# AEMLIC-V1.net
KiCad netlist of a schematic drawn in EAGLE
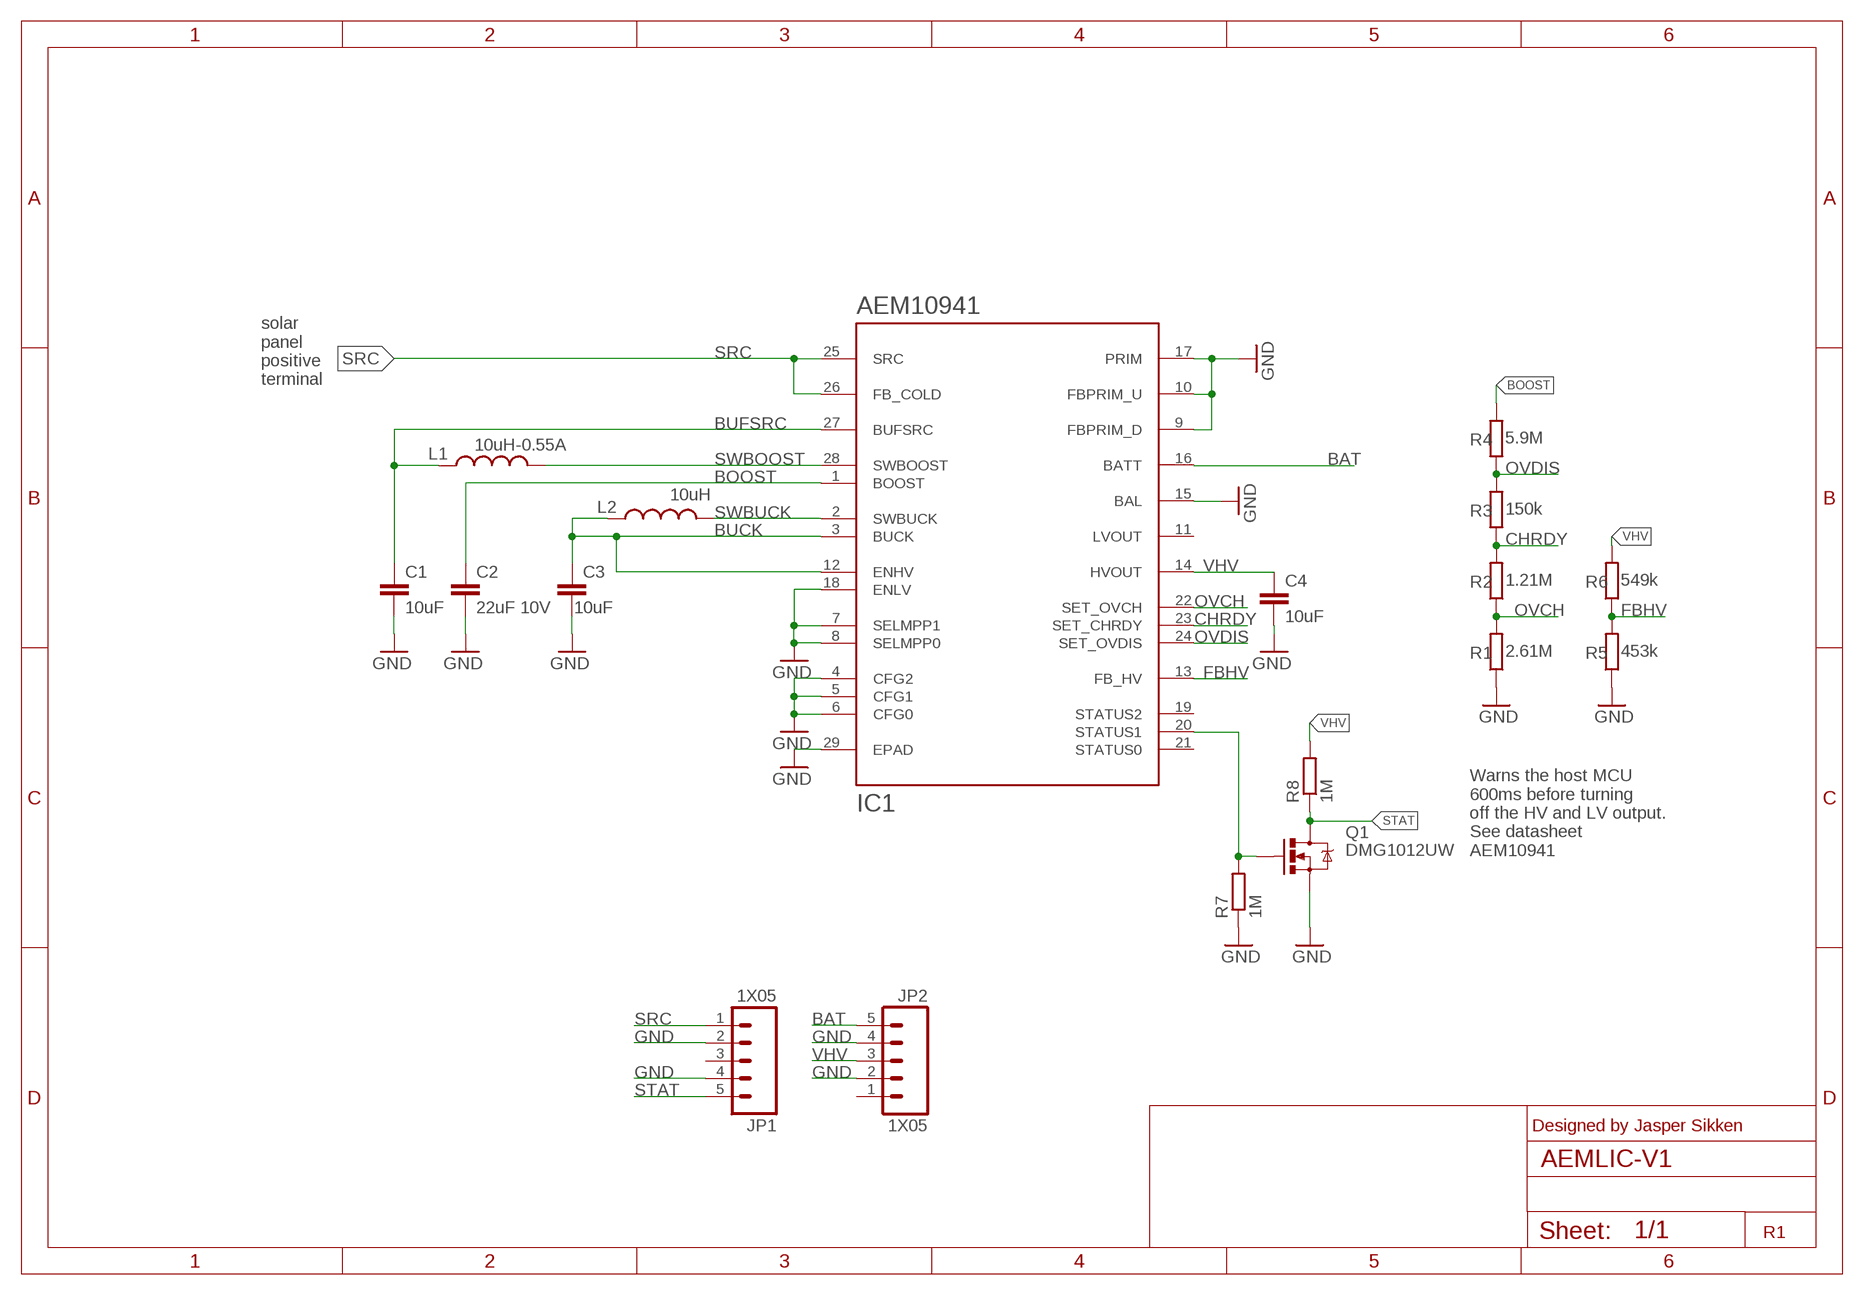
[diagram p0: schematic, sheet 1]

(export (version "E")
  (design (tool "Eeschema 10.0.6"))
  (components
    (comp (ref "C1")
      (value "10uF")
      (footprint "eagle-import:C0603")
      (fields
        (field (name "MF") "Taiyo Yuden")
        (field (name "MPN") "LMK107BBJ106MALT")
        (field (name "MF_1") "KEYSTONE")
        (field (name "MPN_1") "1049P")
      )
      (libsource (lib "eagle-import") (part "C0603_10UF"))
    )
    (comp (ref "C2")
      (value "22uF 10V")
      (footprint "eagle-import:C0603")
      (fields
        (field (name "MF") "Murata")
        (field (name "MPN") "GRM188R61A226ME15D")
        (field (name "MF_1") "TDK")
        (field (name "MPN_1") "CGA5L1X7S1A226M160AC")
      )
      (libsource (lib "eagle-import") (part "C0603_22UF"))
    )
    (comp (ref "C3")
      (value "10uF")
      (footprint "eagle-import:C0603")
      (fields
        (field (name "MF") "Taiyo Yuden")
        (field (name "MPN") "LMK107BBJ106MALT")
        (field (name "MF_1") "KEYSTONE")
        (field (name "MPN_1") "1049P")
      )
      (libsource (lib "eagle-import") (part "C0603_10UF"))
    )
    (comp (ref "C4")
      (value "10uF")
      (footprint "eagle-import:C0603")
      (fields
        (field (name "MF") "Taiyo Yuden")
        (field (name "MPN") "LMK107BBJ106MALT")
        (field (name "MF_1") "KEYSTONE")
        (field (name "MPN_1") "1049P")
      )
      (libsource (lib "eagle-import") (part "C0603_10UF"))
    )
    (comp (ref "IC1")
      (value "AEM10941")
      (footprint "eagle-import:QFN50P505X505X90-28")
      (fields (field (name "MF") "e-peas"))
      (libsource (lib "eagle-import") (part "AEM10941"))
    )
    (comp (ref "JP1")
      (value "1X05")
      (footprint "eagle-import:1X05_2.54MM_ROUND_NOSILK")
      (libsource (lib "eagle-import") (part "1X05"))
    )
    (comp (ref "JP2")
      (value "1X05")
      (footprint "eagle-import:1X05_2.54MM_ROUND_NOSILK")
      (libsource (lib "eagle-import") (part "1X05"))
    )
    (comp (ref "L1")
      (value "10uH-0.55A")
      (footprint "eagle-import:LPS4012")
      (fields
        (field (name "MF") "Coilcraft")
        (field (name "MPN") "LPS4012-103MRB")
        (field (name "MF_1") "BOURNS")
        (field (name "MPN_1") "SRN2009T-100M")
      )
      (libsource (lib "eagle-import") (part "L3.9X3.9_10UH_0.55A"))
    )
    (comp (ref "L2")
      (value "10uH")
      (footprint "eagle-import:L0603")
      (fields
        (field (name "MF") "TDK")
        (field (name "MPN") "MLZ1608M100WT")
        (field (name "MF_1") "TAIYO YUDEN")
        (field (name "MPN_1") "CK2125100M-T")
      )
      (libsource (lib "eagle-import") (part "L0603_10UH"))
    )
    (comp (ref "Q1")
      (value "DMG1012UW")
      (footprint "eagle-import:SOT323")
      (fields (field (name "MF") "Diodes") (field (name "MPN") "DMG1012UW-7"))
      (libsource (lib "eagle-import") (part "MOSFET-N-CHANNEL_DMG1012UW"))
    )
    (comp (ref "R1")
      (value "2.61M")
      (footprint "eagle-import:R0402")
      (fields (field (name "MF") "Walsin") (field (name "MPN") "WR04X1004FTL"))
      (libsource (lib "eagle-import") (part "R0402_1M"))
    )
    (comp (ref "R2")
      (value "1.21M")
      (footprint "eagle-import:R0402")
      (fields (field (name "MF") "Walsin") (field (name "MPN") "WR04X1004FTL"))
      (libsource (lib "eagle-import") (part "R0402_1M"))
    )
    (comp (ref "R3")
      (value "150k")
      (footprint "eagle-import:R0402")
      (fields (field (name "MF") "Walsin") (field (name "MPN") "WR04X1004FTL"))
      (libsource (lib "eagle-import") (part "R0402_1M"))
    )
    (comp (ref "R4")
      (value "5.9M")
      (footprint "eagle-import:R0402")
      (fields (field (name "MF") "Walsin") (field (name "MPN") "WR04X1004FTL"))
      (libsource (lib "eagle-import") (part "R0402_1M"))
    )
    (comp (ref "R5")
      (value "453k")
      (footprint "eagle-import:R0402")
      (fields (field (name "MF") "Walsin") (field (name "MPN") "WR04X1004FTL"))
      (libsource (lib "eagle-import") (part "R0402_1M"))
    )
    (comp (ref "R6")
      (value "549k")
      (footprint "eagle-import:R0402")
      (fields (field (name "MF") "Walsin") (field (name "MPN") "WR04X1004FTL"))
      (libsource (lib "eagle-import") (part "R0402_1M"))
    )
    (comp (ref "R7")
      (value "1M")
      (footprint "eagle-import:R0402")
      (fields (field (name "MF") "Walsin") (field (name "MPN") "WR04X1004FTL"))
      (libsource (lib "eagle-import") (part "R0402_1M"))
    )
    (comp (ref "R8")
      (value "1M")
      (footprint "eagle-import:R0402")
      (fields (field (name "MF") "Walsin") (field (name "MPN") "WR04X1004FTL"))
      (libsource (lib "eagle-import") (part "R0402_1M"))
    )
  )
  (nets
    (net (code "1") (name "/BAT") (class "Default")
      (node (ref "IC1") (pin "16") (pinfunction "BATT_16") (pintype "bidirectional"))
      (node (ref "JP2") (pin "5") (pinfunction "5_5") (pintype "passive"))
    )
    (net (code "2") (name "/BUCK") (class "Default")
      (node (ref "C3") (pin "1") (pinfunction "1_1") (pintype "passive"))
      (node (ref "IC1") (pin "12") (pinfunction "ENHV_12") (pintype "bidirectional"))
      (node (ref "IC1") (pin "3") (pinfunction "BUCK_3") (pintype "bidirectional"))
      (node (ref "L2") (pin "1") (pinfunction "1_1") (pintype "passive"))
    )
    (net (code "3") (name "/BUFSRC") (class "Default")
      (node (ref "C1") (pin "1") (pinfunction "1_1") (pintype "passive"))
      (node (ref "IC1") (pin "27") (pinfunction "BUFSRC_27") (pintype "power_in"))
      (node (ref "L1") (pin "1") (pinfunction "1_1") (pintype "passive"))
    )
    (net (code "4") (name "/CHRDY") (class "Default")
      (node (ref "IC1") (pin "23") (pinfunction "SET_CHRDY_23") (pintype "bidirectional"))
      (node (ref "R2") (pin "2") (pinfunction "2_2") (pintype "passive"))
      (node (ref "R3") (pin "1") (pinfunction "1_1") (pintype "passive"))
    )
    (net (code "5") (name "/FBHV") (class "Default")
      (node (ref "IC1") (pin "13") (pinfunction "FB_HV_13") (pintype "bidirectional"))
      (node (ref "R5") (pin "2") (pinfunction "2_2") (pintype "passive"))
      (node (ref "R6") (pin "1") (pinfunction "1_1") (pintype "passive"))
    )
    (net (code "6") (name "/OVCH") (class "Default")
      (node (ref "IC1") (pin "22") (pinfunction "SET_OVCH_22") (pintype "bidirectional"))
      (node (ref "R1") (pin "2") (pinfunction "2_2") (pintype "passive"))
      (node (ref "R2") (pin "1") (pinfunction "1_1") (pintype "passive"))
    )
    (net (code "7") (name "/OVDIS") (class "Default")
      (node (ref "IC1") (pin "24") (pinfunction "SET_OVDIS_24") (pintype "bidirectional"))
      (node (ref "R3") (pin "2") (pinfunction "2_2") (pintype "passive"))
      (node (ref "R4") (pin "1") (pinfunction "1_1") (pintype "passive"))
    )
    (net (code "8") (name "/SWBOOST") (class "Default")
      (node (ref "IC1") (pin "28") (pinfunction "SWBOOST_28") (pintype "power_in"))
      (node (ref "L1") (pin "2") (pinfunction "2_2") (pintype "passive"))
    )
    (net (code "9") (name "/SWBUCK") (class "Default")
      (node (ref "IC1") (pin "2") (pinfunction "SWBUCK_2") (pintype "bidirectional"))
      (node (ref "L2") (pin "2") (pinfunction "2_2") (pintype "passive"))
    )
    (net (code "10") (name "BOOST") (class "Default")
      (node (ref "C2") (pin "1") (pinfunction "1_1") (pintype "passive"))
      (node (ref "IC1") (pin "1") (pinfunction "BOOST_1") (pintype "bidirectional"))
      (node (ref "R4") (pin "2") (pinfunction "2_2") (pintype "passive"))
    )
    (net (code "11") (name "GND") (class "Default")
      (node (ref "C1") (pin "2") (pinfunction "2_2") (pintype "passive"))
      (node (ref "C2") (pin "2") (pinfunction "2_2") (pintype "passive"))
      (node (ref "C3") (pin "2") (pinfunction "2_2") (pintype "passive"))
      (node (ref "C4") (pin "2") (pinfunction "2_2") (pintype "passive"))
      (node (ref "IC1") (pin "10") (pinfunction "FBPRIM_U_10") (pintype "bidirectional"))
      (node (ref "IC1") (pin "15") (pinfunction "BAL_15") (pintype "bidirectional"))
      (node (ref "IC1") (pin "17") (pinfunction "PRIM_17") (pintype "bidirectional"))
      (node (ref "IC1") (pin "18") (pinfunction "ENLV_18") (pintype "bidirectional"))
      (node (ref "IC1") (pin "29") (pinfunction "EPAD_29") (pintype "power_in"))
      (node (ref "IC1") (pin "4") (pinfunction "CFG2_4") (pintype "bidirectional"))
      (node (ref "IC1") (pin "5") (pinfunction "CFG1_5") (pintype "bidirectional"))
      (node (ref "IC1") (pin "6") (pinfunction "CFG0_6") (pintype "bidirectional"))
      (node (ref "IC1") (pin "7") (pinfunction "SELMPP1_7") (pintype "bidirectional"))
      (node (ref "IC1") (pin "8") (pinfunction "SELMPP0_8") (pintype "bidirectional"))
      (node (ref "IC1") (pin "9") (pinfunction "FBPRIM_D_9") (pintype "bidirectional"))
      (node (ref "JP1") (pin "2") (pinfunction "2_2") (pintype "passive"))
      (node (ref "JP1") (pin "4") (pinfunction "4_4") (pintype "passive"))
      (node (ref "JP2") (pin "2") (pinfunction "2_2") (pintype "passive"))
      (node (ref "JP2") (pin "4") (pinfunction "4_4") (pintype "passive"))
      (node (ref "Q1") (pin "2") (pinfunction "S_2") (pintype "passive"))
      (node (ref "R1") (pin "1") (pinfunction "1_1") (pintype "passive"))
      (node (ref "R5") (pin "1") (pinfunction "1_1") (pintype "passive"))
      (node (ref "R7") (pin "1") (pinfunction "1_1") (pintype "passive"))
    )
    (net (code "12") (name "Net-(IC1-STATUS1)") (class "Default")
      (node (ref "IC1") (pin "20") (pinfunction "STATUS1_20") (pintype "bidirectional"))
      (node (ref "Q1") (pin "1") (pinfunction "G_1") (pintype "passive"))
      (node (ref "R7") (pin "2") (pinfunction "2_2") (pintype "passive"))
    )
    (net (code "13") (name "SRC") (class "Default")
      (node (ref "IC1") (pin "25") (pinfunction "SRC_25") (pintype "power_in"))
      (node (ref "IC1") (pin "26") (pinfunction "FB_COLD_26") (pintype "input"))
      (node (ref "JP1") (pin "1") (pinfunction "1_1") (pintype "passive"))
    )
    (net (code "14") (name "STAT") (class "Default")
      (node (ref "JP1") (pin "5") (pinfunction "5_5") (pintype "passive"))
      (node (ref "Q1") (pin "3") (pinfunction "D_3") (pintype "passive"))
      (node (ref "R8") (pin "1") (pinfunction "1_1") (pintype "passive"))
    )
    (net (code "15") (name "VHV") (class "Default")
      (node (ref "C4") (pin "1") (pinfunction "1_1") (pintype "passive"))
      (node (ref "IC1") (pin "14") (pinfunction "HVOUT_14") (pintype "bidirectional"))
      (node (ref "JP2") (pin "3") (pinfunction "3_3") (pintype "passive"))
      (node (ref "R6") (pin "2") (pinfunction "2_2") (pintype "passive"))
      (node (ref "R8") (pin "2") (pinfunction "2_2") (pintype "passive"))
    )
    (net (code "16") (name "unconnected-(IC1-LVOUT-Pad11)") (class "Default")
      (node (ref "IC1") (pin "11") (pinfunction "LVOUT_11") (pintype "bidirectional"))
    )
    (net (code "17") (name "unconnected-(IC1-STATUS0-Pad21)") (class "Default")
      (node (ref "IC1") (pin "21") (pinfunction "STATUS0_21") (pintype "bidirectional"))
    )
    (net (code "18") (name "unconnected-(IC1-STATUS2-Pad19)") (class "Default")
      (node (ref "IC1") (pin "19") (pinfunction "STATUS2_19") (pintype "bidirectional"))
    )
    (net (code "19") (name "unconnected-(JP1-Pad3)") (class "Default")
      (node (ref "JP1") (pin "3") (pinfunction "3_3") (pintype "passive"))
    )
    (net (code "20") (name "unconnected-(JP2-Pad1)") (class "Default")
      (node (ref "JP2") (pin "1") (pinfunction "1_1") (pintype "passive"))
    )
  )
)
